# MSP_Mini_Voyger_V5.net
KiCad netlist of a schematic drawn in EAGLE
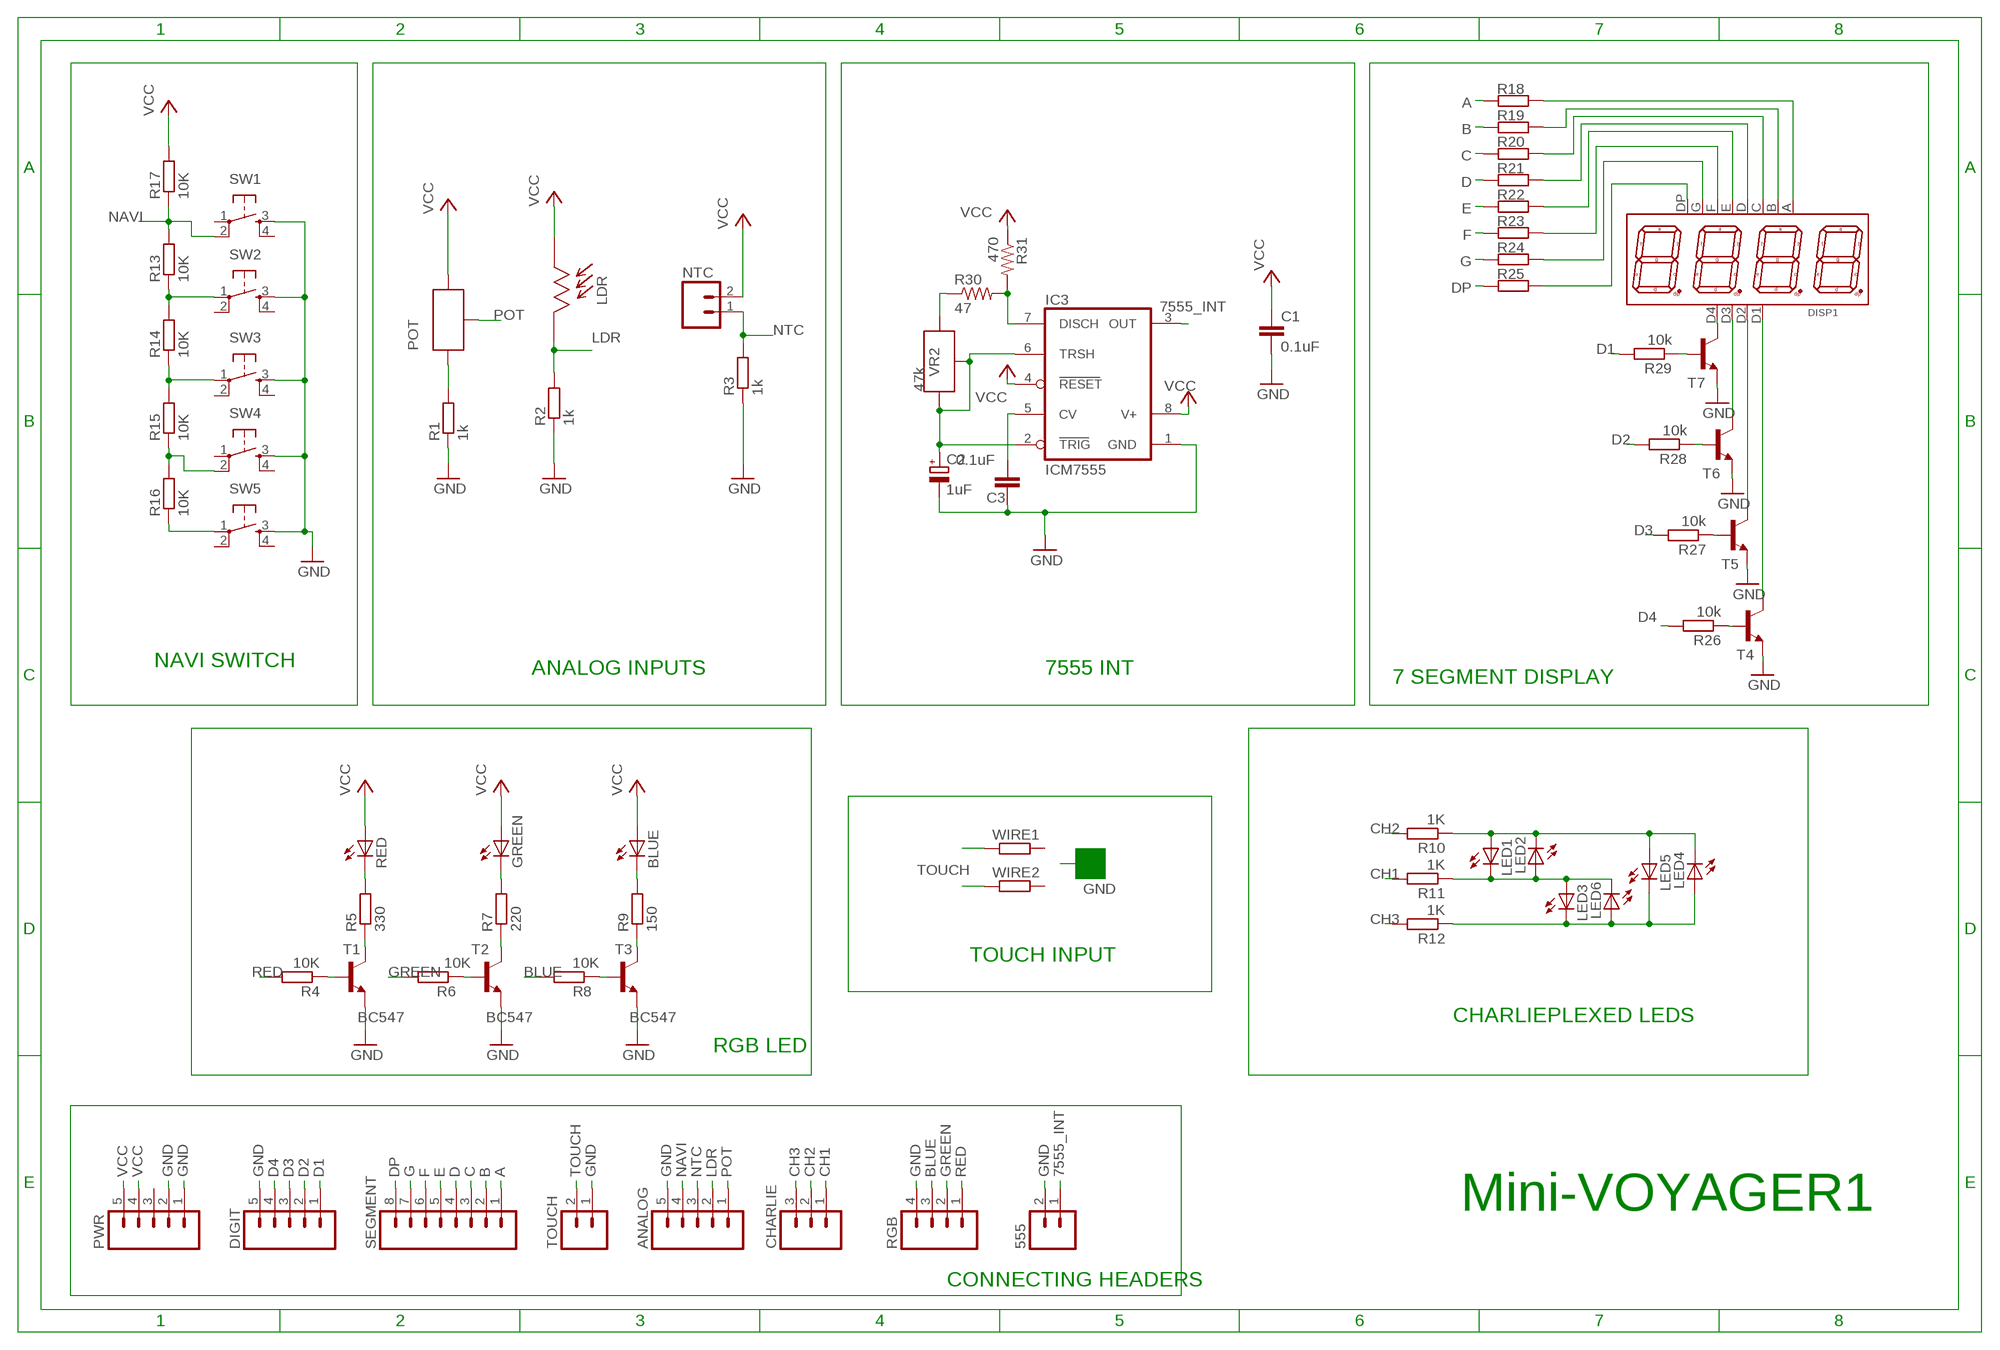
[diagram p0: schematic, sheet 1]

(export (version "E")
  (design (tool "Eeschema 10.0.6"))
  (components
    (comp (ref "555")
      (value "M02")
      (footprint "eagle-import:02P")
      (libsource (lib "eagle-import") (part "con-amp-quick_M02"))
    )
    (comp (ref "ANALOG")
      (value "M05")
      (footprint "eagle-import:05P")
      (libsource (lib "eagle-import") (part "M05"))
    )
    (comp (ref "BLUE")
      (value "LED5MM")
      (footprint "eagle-import:LED5MM")
      (libsource (lib "eagle-import") (part "LED5MM"))
    )
    (comp (ref "C1")
      (value "0.1uF")
      (footprint "eagle-import:C050-024X044")
      (libsource (lib "eagle-import") (part "C-EU050-024X044"))
    )
    (comp (ref "C2")
      (value "1uF")
      (footprint "eagle-import:E2,5-7")
      (libsource (lib "eagle-import") (part "CPOL-EUE2.5-7"))
    )
    (comp (ref "C3")
      (value "0.1uF")
      (footprint "eagle-import:C025-024X044")
      (libsource (lib "eagle-import") (part "C-EU025-024X044"))
    )
    (comp (ref "CHARLIE")
      (value "M03")
      (footprint "eagle-import:03P")
      (libsource (lib "eagle-import") (part "M03"))
    )
    (comp (ref "DIGIT")
      (value "M05")
      (footprint "eagle-import:05P")
      (libsource (lib "eagle-import") (part "M05"))
    )
    (comp (ref "DISP1")
      (value "7-SEG_4D_0.36")
      (footprint "eagle-import:7SEG-4DIG")
      (libsource (lib "eagle-import") (part "7-SEG_4D_0.36"))
    )
    (comp (ref "GREEN")
      (value "LED5MM")
      (footprint "eagle-import:LED5MM")
      (libsource (lib "eagle-import") (part "LED5MM"))
    )
    (comp (ref "IC3")
      (value "ICM7555")
      (footprint "eagle-import:DIL08")
      (fields (field (name "MF") "MAXIM") (field (name "MPN") "ICM7555IPA+"))
      (libsource (lib "eagle-import") (part "ICM7555"))
    )
    (comp (ref "LDR")
      (value "CDSLDR3MM")
      (footprint "eagle-import:LDR3MM")
      (libsource (lib "eagle-import") (part "CDSLDR3MM"))
    )
    (comp (ref "LED1")
      (value "LED3MM")
      (footprint "eagle-import:LED3MM")
      (libsource (lib "eagle-import") (part "CEDT_JANUARY_2015_v7_LED3MM"))
    )
    (comp (ref "LED2")
      (value "LED3MM")
      (footprint "eagle-import:LED3MM")
      (libsource (lib "eagle-import") (part "CEDT_JANUARY_2015_v7_LED3MM"))
    )
    (comp (ref "LED3")
      (value "LED3MM")
      (footprint "eagle-import:LED3MM")
      (libsource (lib "eagle-import") (part "CEDT_JANUARY_2015_v7_LED3MM"))
    )
    (comp (ref "LED4")
      (value "LED3MM")
      (footprint "eagle-import:LED3MM")
      (libsource (lib "eagle-import") (part "CEDT_JANUARY_2015_v7_LED3MM"))
    )
    (comp (ref "LED5")
      (value "LED3MM")
      (footprint "eagle-import:LED3MM")
      (libsource (lib "eagle-import") (part "CEDT_JANUARY_2015_v7_LED3MM"))
    )
    (comp (ref "LED6")
      (value "LED3MM")
      (footprint "eagle-import:LED3MM")
      (libsource (lib "eagle-import") (part "CEDT_JANUARY_2015_v7_LED3MM"))
    )
    (comp (ref "NTC")
      (value "M02")
      (footprint "eagle-import:02P")
      (libsource (lib "eagle-import") (part "M02"))
    )
    (comp (ref "POT")
      (value "POTNORMAL")
      (footprint "eagle-import:RJ9W")
      (libsource (lib "eagle-import") (part "CEDT_JANUARY_2015_v7_POTNORMAL"))
    )
    (comp (ref "PWR")
      (value "M05")
      (footprint "eagle-import:05P")
      (libsource (lib "eagle-import") (part "M05"))
    )
    (comp (ref "R1")
      (value "1k")
      (footprint "eagle-import:0207_10")
      (libsource (lib "eagle-import") (part "R-EU_0207/10"))
    )
    (comp (ref "R2")
      (value "1k")
      (footprint "eagle-import:0207_10")
      (libsource (lib "eagle-import") (part "R-EU_0207/10"))
    )
    (comp (ref "R3")
      (value "1k")
      (footprint "eagle-import:0207_10")
      (libsource (lib "eagle-import") (part "R-EU_0207/10"))
    )
    (comp (ref "R4")
      (value "10K")
      (footprint "eagle-import:0207_7")
      (libsource (lib "eagle-import") (part "R-EU_0207/7"))
    )
    (comp (ref "R5")
      (value "330")
      (footprint "eagle-import:0207_7")
      (libsource (lib "eagle-import") (part "R-EU_0207/7"))
    )
    (comp (ref "R6")
      (value "10K")
      (footprint "eagle-import:0207_7")
      (libsource (lib "eagle-import") (part "R-EU_0207/7"))
    )
    (comp (ref "R7")
      (value "220")
      (footprint "eagle-import:0207_7")
      (libsource (lib "eagle-import") (part "R-EU_0207/7"))
    )
    (comp (ref "R8")
      (value "10K")
      (footprint "eagle-import:0207_7")
      (libsource (lib "eagle-import") (part "R-EU_0207/7"))
    )
    (comp (ref "R9")
      (value "150")
      (footprint "eagle-import:0207_7")
      (libsource (lib "eagle-import") (part "R-EU_0207/7"))
    )
    (comp (ref "R10")
      (value "1K")
      (footprint "eagle-import:0207_10")
      (libsource (lib "eagle-import") (part "R-EU_0207/10"))
    )
    (comp (ref "R11")
      (value "1K")
      (footprint "eagle-import:0207_10")
      (libsource (lib "eagle-import") (part "R-EU_0207/10"))
    )
    (comp (ref "R12")
      (value "1K")
      (footprint "eagle-import:0207_10")
      (libsource (lib "eagle-import") (part "R-EU_0207/10"))
    )
    (comp (ref "R13")
      (value "10K")
      (footprint "eagle-import:0207_10")
      (libsource (lib "eagle-import") (part "R-EU_0207/10"))
    )
    (comp (ref "R14")
      (value "10K")
      (footprint "eagle-import:0207_10")
      (libsource (lib "eagle-import") (part "R-EU_0207/10"))
    )
    (comp (ref "R15")
      (value "10K")
      (footprint "eagle-import:0207_10")
      (libsource (lib "eagle-import") (part "R-EU_0207/10"))
    )
    (comp (ref "R16")
      (value "10K")
      (footprint "eagle-import:0207_10")
      (libsource (lib "eagle-import") (part "R-EU_0207/10"))
    )
    (comp (ref "R17")
      (value "10K")
      (footprint "eagle-import:0207_10")
      (libsource (lib "eagle-import") (part "R-EU_0207/10"))
    )
    (comp (ref "R18")
      (value "1k")
      (footprint "eagle-import:0207_7")
      (libsource (lib "eagle-import") (part "R-EU_0207/7"))
    )
    (comp (ref "R19")
      (value "1k")
      (footprint "eagle-import:0207_7")
      (libsource (lib "eagle-import") (part "R-EU_0207/7"))
    )
    (comp (ref "R20")
      (value "1k")
      (footprint "eagle-import:0207_7")
      (libsource (lib "eagle-import") (part "R-EU_0207/7"))
    )
    (comp (ref "R21")
      (value "1k")
      (footprint "eagle-import:0207_7")
      (libsource (lib "eagle-import") (part "R-EU_0207/7"))
    )
    (comp (ref "R22")
      (value "1k")
      (footprint "eagle-import:0207_7")
      (libsource (lib "eagle-import") (part "R-EU_0207/7"))
    )
    (comp (ref "R23")
      (value "1k")
      (footprint "eagle-import:0207_7")
      (libsource (lib "eagle-import") (part "R-EU_0207/7"))
    )
    (comp (ref "R24")
      (value "1k")
      (footprint "eagle-import:0207_7")
      (libsource (lib "eagle-import") (part "R-EU_0207/7"))
    )
    (comp (ref "R25")
      (value "1k")
      (footprint "eagle-import:0207_7")
      (libsource (lib "eagle-import") (part "R-EU_0207/7"))
    )
    (comp (ref "R26")
      (value "10k")
      (footprint "eagle-import:0207_7")
      (libsource (lib "eagle-import") (part "R-EU_0207/7"))
    )
    (comp (ref "R27")
      (value "10k")
      (footprint "eagle-import:0207_7")
      (libsource (lib "eagle-import") (part "R-EU_0207/7"))
    )
    (comp (ref "R28")
      (value "10k")
      (footprint "eagle-import:0207_7")
      (libsource (lib "eagle-import") (part "R-EU_0207/7"))
    )
    (comp (ref "R29")
      (value "10k")
      (footprint "eagle-import:0207_7")
      (libsource (lib "eagle-import") (part "R-EU_0207/7"))
    )
    (comp (ref "R30")
      (value "47")
      (footprint "eagle-import:0207_7")
      (libsource (lib "eagle-import") (part "R-US_0207/7"))
    )
    (comp (ref "R31")
      (value "470")
      (footprint "eagle-import:0207_7")
      (libsource (lib "eagle-import") (part "R-US_0207/7"))
    )
    (comp (ref "RED")
      (value "LED5MM")
      (footprint "eagle-import:LED5MM")
      (libsource (lib "eagle-import") (part "LED5MM"))
    )
    (comp (ref "RGB")
      (value "M04")
      (footprint "eagle-import:04P")
      (libsource (lib "eagle-import") (part "M04"))
    )
    (comp (ref "SEGMENT")
      (value "M08")
      (footprint "eagle-import:08P")
      (libsource (lib "eagle-import") (part "M08"))
    )
    (comp (ref "SW1")
      (value "OMRON_SWITCH_10-XX")
      (footprint "eagle-import:B3F-10XX")
      (libsource (lib "eagle-import") (part "OMRON_SWITCH_10-XX"))
    )
    (comp (ref "SW2")
      (value "OMRON_SWITCH_10-XX")
      (footprint "eagle-import:B3F-10XX")
      (libsource (lib "eagle-import") (part "OMRON_SWITCH_10-XX"))
    )
    (comp (ref "SW3")
      (value "OMRON_SWITCH_10-XX")
      (footprint "eagle-import:B3F-10XX")
      (libsource (lib "eagle-import") (part "OMRON_SWITCH_10-XX"))
    )
    (comp (ref "SW4")
      (value "OMRON_SWITCH_10-XX")
      (footprint "eagle-import:B3F-10XX")
      (libsource (lib "eagle-import") (part "OMRON_SWITCH_10-XX"))
    )
    (comp (ref "SW5")
      (value "OMRON_SWITCH_10-XX")
      (footprint "eagle-import:B3F-10XX")
      (libsource (lib "eagle-import") (part "OMRON_SWITCH_10-XX"))
    )
    (comp (ref "T1")
      (value "BC547")
      (footprint "eagle-import:TO92")
      (libsource (lib "eagle-import") (part "BC547"))
    )
    (comp (ref "T2")
      (value "BC547")
      (footprint "eagle-import:TO92")
      (libsource (lib "eagle-import") (part "BC547"))
    )
    (comp (ref "T3")
      (value "BC547")
      (footprint "eagle-import:TO92")
      (libsource (lib "eagle-import") (part "BC547"))
    )
    (comp (ref "T4")
      (value "BC547")
      (footprint "eagle-import:TO92")
      (libsource (lib "eagle-import") (part "BC547"))
    )
    (comp (ref "T5")
      (value "BC547")
      (footprint "eagle-import:TO92")
      (libsource (lib "eagle-import") (part "BC547"))
    )
    (comp (ref "T6")
      (value "BC547")
      (footprint "eagle-import:TO92")
      (libsource (lib "eagle-import") (part "BC547"))
    )
    (comp (ref "T7")
      (value "BC547")
      (footprint "eagle-import:TO92")
      (libsource (lib "eagle-import") (part "BC547"))
    )
    (comp (ref "TOUCH")
      (value "M02")
      (footprint "eagle-import:02P")
      (libsource (lib "eagle-import") (part "M02"))
    )
    (comp (ref "VR2")
      (value "47k")
      (footprint "eagle-import:RJ9W")
      (libsource (lib "eagle-import") (part "POTNORMAL"))
    )
    (comp (ref "WIRE1")
      (value "R-EU_0207/15")
      (footprint "eagle-import:0207_15")
      (libsource (lib "eagle-import") (part "R-EU_0207/15"))
    )
    (comp (ref "WIRE2")
      (value "R-EU_0207/15")
      (footprint "eagle-import:0207_15")
      (libsource (lib "eagle-import") (part "R-EU_0207/15"))
    )
  )
  (nets
    (net (code "1") (name "/7555_INT") (class "Default")
      (node (ref "555") (pin "1") (pinfunction "1_1") (pintype "passive"))
      (node (ref "IC3") (pin "3") (pinfunction "OUT_3") (pintype "output"))
    )
    (net (code "2") (name "/A") (class "Default")
      (node (ref "R18") (pin "2") (pinfunction "2_2") (pintype "passive"))
      (node (ref "SEGMENT") (pin "1") (pinfunction "1_1") (pintype "passive"))
    )
    (net (code "3") (name "/B") (class "Default")
      (node (ref "R19") (pin "2") (pinfunction "2_2") (pintype "passive"))
      (node (ref "SEGMENT") (pin "2") (pinfunction "2_2") (pintype "passive"))
    )
    (net (code "4") (name "/BLUE") (class "Default")
      (node (ref "R8") (pin "2") (pinfunction "2_2") (pintype "passive"))
      (node (ref "RGB") (pin "3") (pinfunction "3_3") (pintype "passive"))
    )
    (net (code "5") (name "/C") (class "Default")
      (node (ref "R20") (pin "2") (pinfunction "2_2") (pintype "passive"))
      (node (ref "SEGMENT") (pin "3") (pinfunction "3_3") (pintype "passive"))
    )
    (net (code "6") (name "/CH1") (class "Default")
      (node (ref "CHARLIE") (pin "1") (pinfunction "1_1") (pintype "passive"))
      (node (ref "R11") (pin "2") (pinfunction "2_2") (pintype "passive"))
    )
    (net (code "7") (name "/CH2") (class "Default")
      (node (ref "CHARLIE") (pin "2") (pinfunction "2_2") (pintype "passive"))
      (node (ref "R10") (pin "2") (pinfunction "2_2") (pintype "passive"))
    )
    (net (code "8") (name "/CH3") (class "Default")
      (node (ref "CHARLIE") (pin "3") (pinfunction "3_3") (pintype "passive"))
      (node (ref "R12") (pin "2") (pinfunction "2_2") (pintype "passive"))
    )
    (net (code "9") (name "/D") (class "Default")
      (node (ref "R21") (pin "2") (pinfunction "2_2") (pintype "passive"))
      (node (ref "SEGMENT") (pin "4") (pinfunction "4_4") (pintype "passive"))
    )
    (net (code "10") (name "/D1") (class "Default")
      (node (ref "DIGIT") (pin "1") (pinfunction "1_1") (pintype "passive"))
      (node (ref "R29") (pin "2") (pinfunction "2_2") (pintype "passive"))
    )
    (net (code "11") (name "/D2") (class "Default")
      (node (ref "DIGIT") (pin "2") (pinfunction "2_2") (pintype "passive"))
      (node (ref "R28") (pin "2") (pinfunction "2_2") (pintype "passive"))
    )
    (net (code "12") (name "/D3") (class "Default")
      (node (ref "DIGIT") (pin "3") (pinfunction "3_3") (pintype "passive"))
      (node (ref "R27") (pin "2") (pinfunction "2_2") (pintype "passive"))
    )
    (net (code "13") (name "/D4") (class "Default")
      (node (ref "DIGIT") (pin "4") (pinfunction "4_4") (pintype "passive"))
      (node (ref "R26") (pin "2") (pinfunction "2_2") (pintype "passive"))
    )
    (net (code "14") (name "/DP") (class "Default")
      (node (ref "R25") (pin "2") (pinfunction "2_2") (pintype "passive"))
      (node (ref "SEGMENT") (pin "8") (pinfunction "8_8") (pintype "passive"))
    )
    (net (code "15") (name "/E") (class "Default")
      (node (ref "R22") (pin "2") (pinfunction "2_2") (pintype "passive"))
      (node (ref "SEGMENT") (pin "5") (pinfunction "5_5") (pintype "passive"))
    )
    (net (code "16") (name "/F") (class "Default")
      (node (ref "R23") (pin "2") (pinfunction "2_2") (pintype "passive"))
      (node (ref "SEGMENT") (pin "6") (pinfunction "6_6") (pintype "passive"))
    )
    (net (code "17") (name "/G") (class "Default")
      (node (ref "R24") (pin "2") (pinfunction "2_2") (pintype "passive"))
      (node (ref "SEGMENT") (pin "7") (pinfunction "7_7") (pintype "passive"))
    )
    (net (code "18") (name "/GREEN") (class "Default")
      (node (ref "R6") (pin "2") (pinfunction "2_2") (pintype "passive"))
      (node (ref "RGB") (pin "2") (pinfunction "2_2") (pintype "passive"))
    )
    (net (code "19") (name "/LDR") (class "Default")
      (node (ref "ANALOG") (pin "2") (pinfunction "2_2") (pintype "passive"))
      (node (ref "LDR") (pin "P$2") (pinfunction "P$2_P$2") (pintype "bidirectional"))
      (node (ref "R2") (pin "2") (pinfunction "2_2") (pintype "passive"))
    )
    (net (code "20") (name "/NAVI") (class "Default")
      (node (ref "ANALOG") (pin "4") (pinfunction "4_4") (pintype "passive"))
      (node (ref "R13") (pin "2") (pinfunction "2_2") (pintype "passive"))
      (node (ref "R17") (pin "1") (pinfunction "1_1") (pintype "passive"))
      (node (ref "SW1") (pin "2") (pinfunction "P1_2") (pintype "passive"))
    )
    (net (code "21") (name "/NTC") (class "Default")
      (node (ref "ANALOG") (pin "3") (pinfunction "3_3") (pintype "passive"))
      (node (ref "NTC") (pin "1") (pinfunction "1_1") (pintype "passive"))
      (node (ref "R3") (pin "2") (pinfunction "2_2") (pintype "passive"))
    )
    (net (code "22") (name "/POT") (class "Default")
      (node (ref "ANALOG") (pin "1") (pinfunction "1_1") (pintype "passive"))
      (node (ref "POT") (pin "S") (pinfunction "S_S") (pintype "passive"))
    )
    (net (code "23") (name "/RED") (class "Default")
      (node (ref "R4") (pin "2") (pinfunction "2_2") (pintype "passive"))
      (node (ref "RGB") (pin "1") (pinfunction "1_1") (pintype "passive"))
    )
    (net (code "24") (name "/TOUCH") (class "Default")
      (node (ref "TOUCH") (pin "2") (pinfunction "2_2") (pintype "passive"))
      (node (ref "WIRE1") (pin "1") (pinfunction "1_1") (pintype "passive"))
      (node (ref "WIRE2") (pin "1") (pinfunction "1_1") (pintype "passive"))
    )
    (net (code "25") (name "GND") (class "Default")
      (node (ref "555") (pin "2") (pinfunction "2_2") (pintype "passive"))
      (node (ref "ANALOG") (pin "5") (pinfunction "5_5") (pintype "passive"))
      (node (ref "C1") (pin "2") (pinfunction "2_2") (pintype "passive"))
      (node (ref "C2") (pin "-") (pinfunction "-_-") (pintype "passive"))
      (node (ref "C3") (pin "2") (pinfunction "2_2") (pintype "passive"))
      (node (ref "DIGIT") (pin "5") (pinfunction "5_5") (pintype "passive"))
      (node (ref "IC3") (pin "1") (pinfunction "GND_1") (pintype "power_in"))
      (node (ref "PWR") (pin "1") (pinfunction "1_1") (pintype "passive"))
      (node (ref "PWR") (pin "2") (pinfunction "2_2") (pintype "passive"))
      (node (ref "R1") (pin "1") (pinfunction "1_1") (pintype "passive"))
      (node (ref "R2") (pin "1") (pinfunction "1_1") (pintype "passive"))
      (node (ref "R3") (pin "1") (pinfunction "1_1") (pintype "passive"))
      (node (ref "RGB") (pin "4") (pinfunction "4_4") (pintype "passive"))
      (node (ref "SW1") (pin "3") (pinfunction "S_3") (pintype "passive"))
      (node (ref "SW2") (pin "3") (pinfunction "S_3") (pintype "passive"))
      (node (ref "SW3") (pin "3") (pinfunction "S_3") (pintype "passive"))
      (node (ref "SW4") (pin "3") (pinfunction "S_3") (pintype "passive"))
      (node (ref "SW5") (pin "3") (pinfunction "S_3") (pintype "passive"))
      (node (ref "T1") (pin "1") (pinfunction "E_1") (pintype "passive"))
      (node (ref "T2") (pin "1") (pinfunction "E_1") (pintype "passive"))
      (node (ref "T3") (pin "1") (pinfunction "E_1") (pintype "passive"))
      (node (ref "T4") (pin "1") (pinfunction "E_1") (pintype "passive"))
      (node (ref "T5") (pin "1") (pinfunction "E_1") (pintype "passive"))
      (node (ref "T6") (pin "1") (pinfunction "E_1") (pintype "passive"))
      (node (ref "T7") (pin "1") (pinfunction "E_1") (pintype "passive"))
      (node (ref "TOUCH") (pin "1") (pinfunction "1_1") (pintype "passive"))
    )
    (net (code "26") (name "Net-(BLUE-C)") (class "Default")
      (node (ref "BLUE") (pin "K") (pinfunction "C_K") (pintype "passive"))
      (node (ref "R9") (pin "2") (pinfunction "2_2") (pintype "passive"))
    )
    (net (code "27") (name "Net-(DISP1-PadA)") (class "Default")
      (node (ref "DISP1") (pin "A") (pinfunction "A_A") (pintype "bidirectional"))
      (node (ref "R18") (pin "1") (pinfunction "1_1") (pintype "passive"))
    )
    (net (code "28") (name "Net-(DISP1-PadB)") (class "Default")
      (node (ref "DISP1") (pin "B") (pinfunction "B_B") (pintype "bidirectional"))
      (node (ref "R19") (pin "1") (pinfunction "1_1") (pintype "passive"))
    )
    (net (code "29") (name "Net-(DISP1-PadC)") (class "Default")
      (node (ref "DISP1") (pin "C") (pinfunction "C_C") (pintype "bidirectional"))
      (node (ref "R20") (pin "1") (pinfunction "1_1") (pintype "passive"))
    )
    (net (code "30") (name "Net-(DISP1-PadD)") (class "Default")
      (node (ref "DISP1") (pin "D") (pinfunction "D_D") (pintype "bidirectional"))
      (node (ref "R21") (pin "1") (pinfunction "1_1") (pintype "passive"))
    )
    (net (code "31") (name "Net-(DISP1-PadDP)") (class "Default")
      (node (ref "DISP1") (pin "DP") (pinfunction "DP_DP") (pintype "bidirectional"))
      (node (ref "R25") (pin "1") (pinfunction "1_1") (pintype "passive"))
    )
    (net (code "32") (name "Net-(DISP1-PadE)") (class "Default")
      (node (ref "DISP1") (pin "E") (pinfunction "E_E") (pintype "bidirectional"))
      (node (ref "R22") (pin "1") (pinfunction "1_1") (pintype "passive"))
    )
    (net (code "33") (name "Net-(DISP1-PadF)") (class "Default")
      (node (ref "DISP1") (pin "F") (pinfunction "F_F") (pintype "bidirectional"))
      (node (ref "R23") (pin "1") (pinfunction "1_1") (pintype "passive"))
    )
    (net (code "34") (name "Net-(DISP1-PadG)") (class "Default")
      (node (ref "DISP1") (pin "G") (pinfunction "G_G") (pintype "bidirectional"))
      (node (ref "R24") (pin "1") (pinfunction "1_1") (pintype "passive"))
    )
    (net (code "35") (name "Net-(GREEN-C)") (class "Default")
      (node (ref "GREEN") (pin "K") (pinfunction "C_K") (pintype "passive"))
      (node (ref "R7") (pin "2") (pinfunction "2_2") (pintype "passive"))
    )
    (net (code "36") (name "Net-(IC3-CV)") (class "Default")
      (node (ref "C3") (pin "1") (pinfunction "1_1") (pintype "passive"))
      (node (ref "IC3") (pin "5") (pinfunction "CV_5") (pintype "passive"))
    )
    (net (code "37") (name "Net-(IC3-DISCH)") (class "Default")
      (node (ref "IC3") (pin "7") (pinfunction "DISCH_7") (pintype "input"))
      (node (ref "R30") (pin "2") (pinfunction "2_2") (pintype "passive"))
      (node (ref "R31") (pin "2") (pinfunction "2_2") (pintype "passive"))
    )
    (net (code "38") (name "Net-(IC3-TRIG)") (class "Default")
      (node (ref "C2") (pin "+") (pinfunction "+_+") (pintype "passive"))
      (node (ref "IC3") (pin "2") (pinfunction "TRIG_2") (pintype "bidirectional"))
      (node (ref "IC3") (pin "6") (pinfunction "TRSH_6") (pintype "input"))
      (node (ref "VR2") (pin "E") (pinfunction "E_E") (pintype "passive"))
      (node (ref "VR2") (pin "S") (pinfunction "S_S") (pintype "passive"))
    )
    (net (code "39") (name "Net-(LED1-C)") (class "Default")
      (node (ref "LED1") (pin "K") (pinfunction "C_K") (pintype "passive"))
      (node (ref "LED2") (pin "A") (pinfunction "A_A") (pintype "passive"))
      (node (ref "LED3") (pin "A") (pinfunction "A_A") (pintype "passive"))
      (node (ref "LED6") (pin "K") (pinfunction "C_K") (pintype "passive"))
      (node (ref "R11") (pin "1") (pinfunction "1_1") (pintype "passive"))
    )
    (net (code "40") (name "Net-(LED2-C)") (class "Default")
      (node (ref "LED1") (pin "A") (pinfunction "A_A") (pintype "passive"))
      (node (ref "LED2") (pin "K") (pinfunction "C_K") (pintype "passive"))
      (node (ref "LED4") (pin "K") (pinfunction "C_K") (pintype "passive"))
      (node (ref "LED5") (pin "A") (pinfunction "A_A") (pintype "passive"))
      (node (ref "R10") (pin "1") (pinfunction "1_1") (pintype "passive"))
    )
    (net (code "41") (name "Net-(LED3-C)") (class "Default")
      (node (ref "LED3") (pin "K") (pinfunction "C_K") (pintype "passive"))
      (node (ref "LED4") (pin "A") (pinfunction "A_A") (pintype "passive"))
      (node (ref "LED5") (pin "K") (pinfunction "C_K") (pintype "passive"))
      (node (ref "LED6") (pin "A") (pinfunction "A_A") (pintype "passive"))
      (node (ref "R12") (pin "1") (pinfunction "1_1") (pintype "passive"))
    )
    (net (code "42") (name "Net-(POT-PadE)") (class "Default")
      (node (ref "POT") (pin "E") (pinfunction "E_E") (pintype "passive"))
      (node (ref "R1") (pin "2") (pinfunction "2_2") (pintype "passive"))
    )
    (net (code "43") (name "Net-(R30-Pad1)") (class "Default")
      (node (ref "R30") (pin "1") (pinfunction "1_1") (pintype "passive"))
      (node (ref "VR2") (pin "A") (pinfunction "A_A") (pintype "passive"))
    )
    (net (code "44") (name "Net-(RED-C)") (class "Default")
      (node (ref "R5") (pin "2") (pinfunction "2_2") (pintype "passive"))
      (node (ref "RED") (pin "K") (pinfunction "C_K") (pintype "passive"))
    )
    (net (code "45") (name "Net-(SW2-P)") (class "Default")
      (node (ref "R13") (pin "1") (pinfunction "1_1") (pintype "passive"))
      (node (ref "R14") (pin "2") (pinfunction "2_2") (pintype "passive"))
      (node (ref "SW2") (pin "1") (pinfunction "P_1") (pintype "passive"))
    )
    (net (code "46") (name "Net-(SW3-P)") (class "Default")
      (node (ref "R14") (pin "1") (pinfunction "1_1") (pintype "passive"))
      (node (ref "R15") (pin "2") (pinfunction "2_2") (pintype "passive"))
      (node (ref "SW3") (pin "1") (pinfunction "P_1") (pintype "passive"))
    )
    (net (code "47") (name "Net-(SW4-P1)") (class "Default")
      (node (ref "R15") (pin "1") (pinfunction "1_1") (pintype "passive"))
      (node (ref "R16") (pin "2") (pinfunction "2_2") (pintype "passive"))
      (node (ref "SW4") (pin "2") (pinfunction "P1_2") (pintype "passive"))
    )
    (net (code "48") (name "Net-(SW5-P)") (class "Default")
      (node (ref "R16") (pin "1") (pinfunction "1_1") (pintype "passive"))
      (node (ref "SW5") (pin "1") (pinfunction "P_1") (pintype "passive"))
    )
    (net (code "49") (name "Net-(T1-B)") (class "Default")
      (node (ref "R4") (pin "1") (pinfunction "1_1") (pintype "passive"))
      (node (ref "T1") (pin "2") (pinfunction "B_2") (pintype "passive"))
    )
    (net (code "50") (name "Net-(T1-C)") (class "Default")
      (node (ref "R5") (pin "1") (pinfunction "1_1") (pintype "passive"))
      (node (ref "T1") (pin "3") (pinfunction "C_3") (pintype "passive"))
    )
    (net (code "51") (name "Net-(T2-B)") (class "Default")
      (node (ref "R6") (pin "1") (pinfunction "1_1") (pintype "passive"))
      (node (ref "T2") (pin "2") (pinfunction "B_2") (pintype "passive"))
    )
    (net (code "52") (name "Net-(T2-C)") (class "Default")
      (node (ref "R7") (pin "1") (pinfunction "1_1") (pintype "passive"))
      (node (ref "T2") (pin "3") (pinfunction "C_3") (pintype "passive"))
    )
    (net (code "53") (name "Net-(T3-B)") (class "Default")
      (node (ref "R8") (pin "1") (pinfunction "1_1") (pintype "passive"))
      (node (ref "T3") (pin "2") (pinfunction "B_2") (pintype "passive"))
    )
    (net (code "54") (name "Net-(T3-C)") (class "Default")
      (node (ref "R9") (pin "1") (pinfunction "1_1") (pintype "passive"))
      (node (ref "T3") (pin "3") (pinfunction "C_3") (pintype "passive"))
    )
    (net (code "55") (name "Net-(T4-B)") (class "Default")
      (node (ref "R26") (pin "1") (pinfunction "1_1") (pintype "passive"))
      (node (ref "T4") (pin "2") (pinfunction "B_2") (pintype "passive"))
    )
    (net (code "56") (name "Net-(T4-C)") (class "Default")
      (node (ref "DISP1") (pin "D1") (pinfunction "D1_D1") (pintype "bidirectional"))
      (node (ref "T4") (pin "3") (pinfunction "C_3") (pintype "passive"))
    )
    (net (code "57") (name "Net-(T5-B)") (class "Default")
      (node (ref "R27") (pin "1") (pinfunction "1_1") (pintype "passive"))
      (node (ref "T5") (pin "2") (pinfunction "B_2") (pintype "passive"))
    )
    (net (code "58") (name "Net-(T5-C)") (class "Default")
      (node (ref "DISP1") (pin "D2") (pinfunction "D2_D2") (pintype "bidirectional"))
      (node (ref "T5") (pin "3") (pinfunction "C_3") (pintype "passive"))
    )
    (net (code "59") (name "Net-(T6-B)") (class "Default")
      (node (ref "R28") (pin "1") (pinfunction "1_1") (pintype "passive"))
      (node (ref "T6") (pin "2") (pinfunction "B_2") (pintype "passive"))
    )
    (net (code "60") (name "Net-(T6-C)") (class "Default")
      (node (ref "DISP1") (pin "D3") (pinfunction "D3_D3") (pintype "bidirectional"))
      (node (ref "T6") (pin "3") (pinfunction "C_3") (pintype "passive"))
    )
    (net (code "61") (name "Net-(T7-B)") (class "Default")
      (node (ref "R29") (pin "1") (pinfunction "1_1") (pintype "passive"))
      (node (ref "T7") (pin "2") (pinfunction "B_2") (pintype "passive"))
    )
    (net (code "62") (name "Net-(T7-C)") (class "Default")
      (node (ref "DISP1") (pin "D4") (pinfunction "D4_D4") (pintype "bidirectional"))
      (node (ref "T7") (pin "3") (pinfunction "C_3") (pintype "passive"))
    )
    (net (code "63") (name "VCC") (class "Default")
      (node (ref "BLUE") (pin "A") (pinfunction "A_A") (pintype "passive"))
      (node (ref "C1") (pin "1") (pinfunction "1_1") (pintype "passive"))
      (node (ref "GREEN") (pin "A") (pinfunction "A_A") (pintype "passive"))
      (node (ref "IC3") (pin "4") (pinfunction "RESET_4") (pintype "input"))
      (node (ref "IC3") (pin "8") (pinfunction "V+_8") (pintype "power_in"))
      (node (ref "LDR") (pin "P$1") (pinfunction "P$1_P$1") (pintype "bidirectional"))
      (node (ref "NTC") (pin "2") (pinfunction "2_2") (pintype "passive"))
      (node (ref "POT") (pin "A") (pinfunction "A_A") (pintype "passive"))
      (node (ref "PWR") (pin "4") (pinfunction "4_4") (pintype "passive"))
      (node (ref "PWR") (pin "5") (pinfunction "5_5") (pintype "passive"))
      (node (ref "R17") (pin "2") (pinfunction "2_2") (pintype "passive"))
      (node (ref "R31") (pin "1") (pinfunction "1_1") (pintype "passive"))
      (node (ref "RED") (pin "A") (pinfunction "A_A") (pintype "passive"))
    )
    (net (code "64") (name "unconnected-(PWR-Pad3)") (class "Default")
      (node (ref "PWR") (pin "3") (pinfunction "3_3") (pintype "passive"))
    )
    (net (code "65") (name "unconnected-(SW1-P-Pad1)") (class "Default")
      (node (ref "SW1") (pin "1") (pinfunction "P_1") (pintype "passive"))
    )
    (net (code "66") (name "unconnected-(SW1-S1-Pad4)") (class "Default")
      (node (ref "SW1") (pin "4") (pinfunction "S1_4") (pintype "passive"))
    )
    (net (code "67") (name "unconnected-(SW2-P1-Pad2)") (class "Default")
      (node (ref "SW2") (pin "2") (pinfunction "P1_2") (pintype "passive"))
    )
    (net (code "68") (name "unconnected-(SW2-S1-Pad4)") (class "Default")
      (node (ref "SW2") (pin "4") (pinfunction "S1_4") (pintype "passive"))
    )
    (net (code "69") (name "unconnected-(SW3-P1-Pad2)") (class "Default")
      (node (ref "SW3") (pin "2") (pinfunction "P1_2") (pintype "passive"))
    )
    (net (code "70") (name "unconnected-(SW3-S1-Pad4)") (class "Default")
      (node (ref "SW3") (pin "4") (pinfunction "S1_4") (pintype "passive"))
    )
    (net (code "71") (name "unconnected-(SW4-P-Pad1)") (class "Default")
      (node (ref "SW4") (pin "1") (pinfunction "P_1") (pintype "passive"))
    )
    (net (code "72") (name "unconnected-(SW4-S1-Pad4)") (class "Default")
      (node (ref "SW4") (pin "4") (pinfunction "S1_4") (pintype "passive"))
    )
    (net (code "73") (name "unconnected-(SW5-P1-Pad2)") (class "Default")
      (node (ref "SW5") (pin "2") (pinfunction "P1_2") (pintype "passive"))
    )
    (net (code "74") (name "unconnected-(SW5-S1-Pad4)") (class "Default")
      (node (ref "SW5") (pin "4") (pinfunction "S1_4") (pintype "passive"))
    )
    (net (code "75") (name "unconnected-(WIRE1-Pad2)") (class "Default")
      (node (ref "WIRE1") (pin "2") (pinfunction "2_2") (pintype "passive"))
    )
    (net (code "76") (name "unconnected-(WIRE2-Pad2)") (class "Default")
      (node (ref "WIRE2") (pin "2") (pinfunction "2_2") (pintype "passive"))
    )
  )
)
